# AccelRecorder.net
KiCad netlist of a schematic drawn in EAGLE
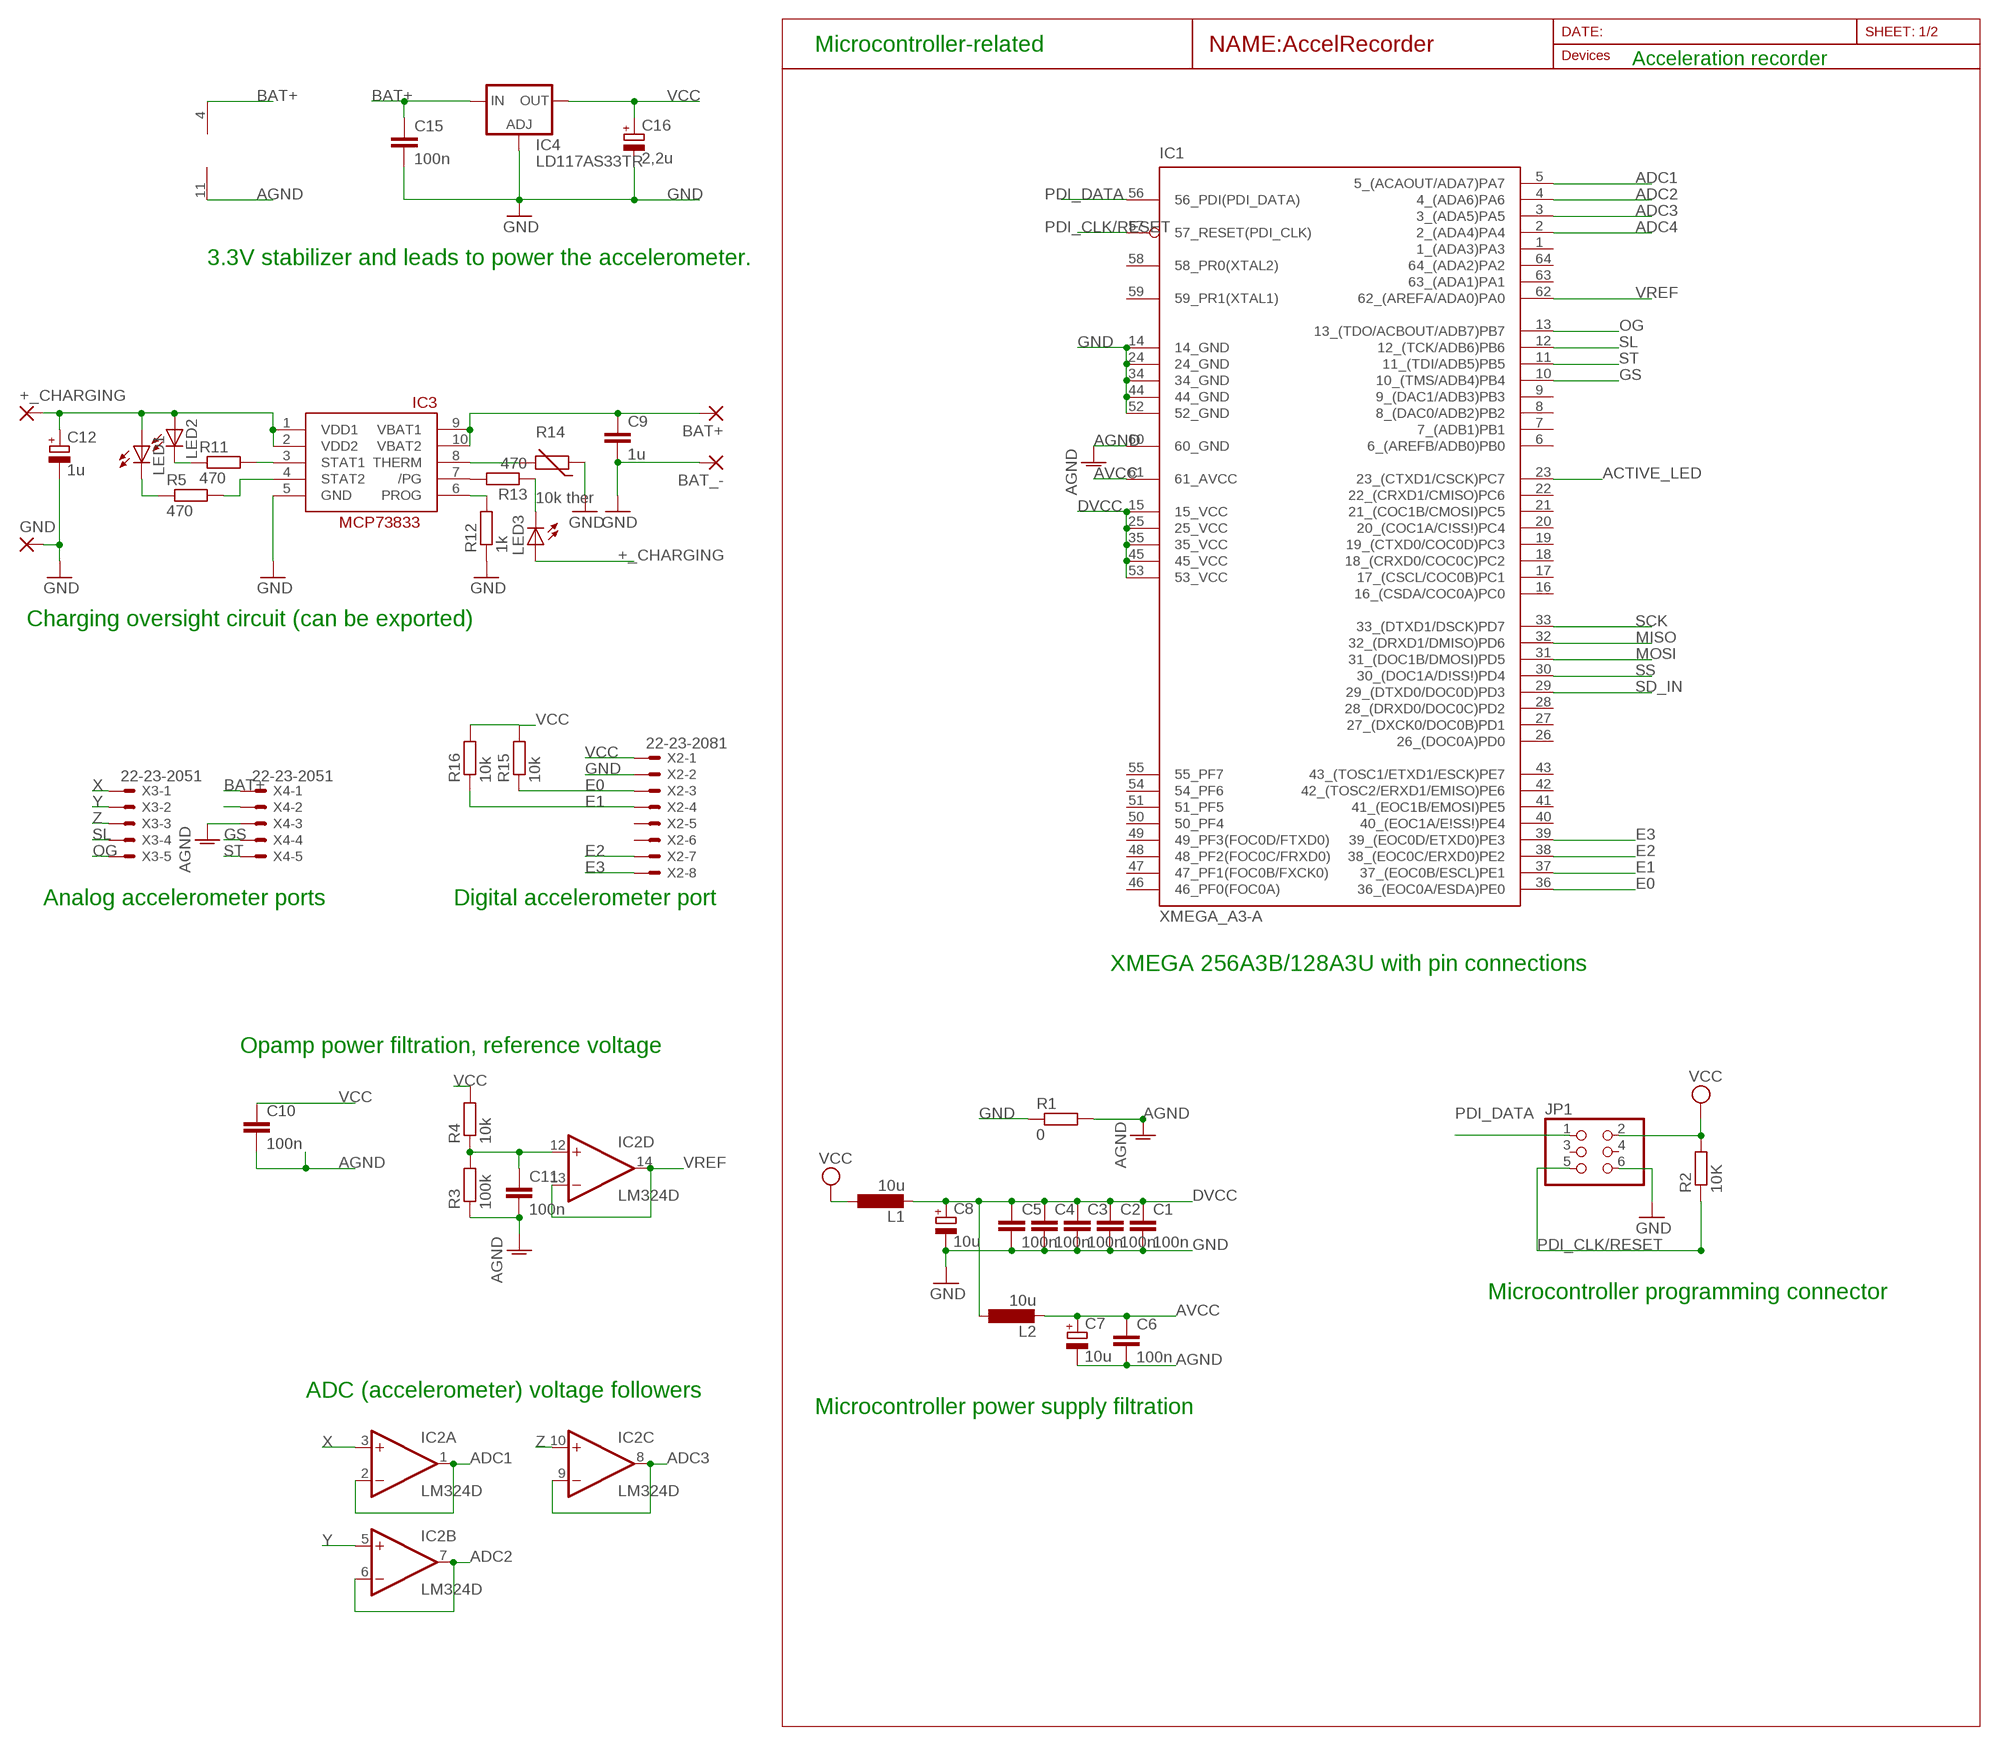
[diagram p0: schematic, sheet 1]
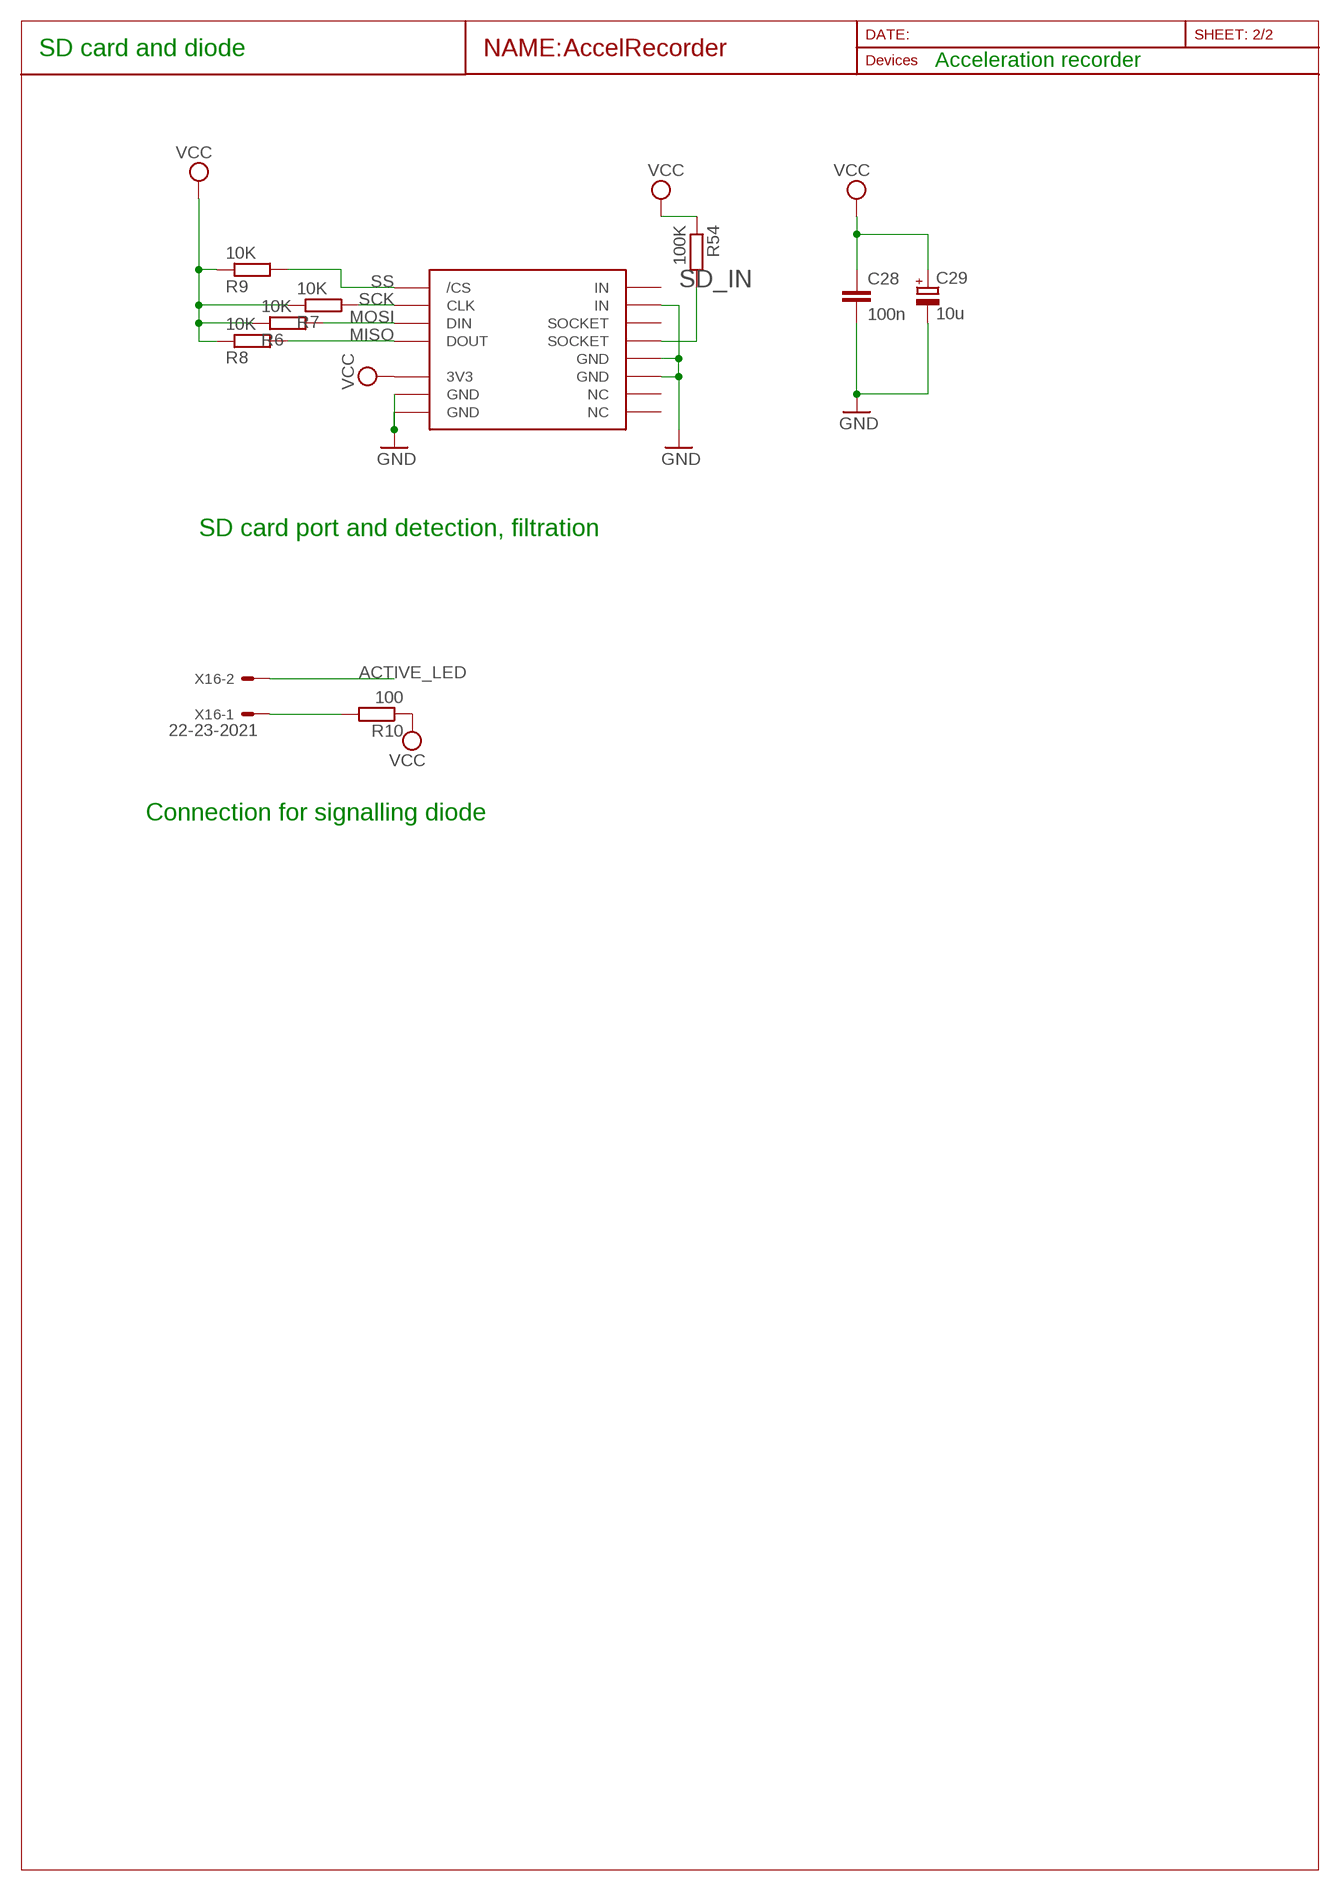
[diagram p1: schematic, sheet 2]

(export (version "E")
  (design (tool "Eeschema 10.0.6"))
  (components
    (comp (ref "+_CHARGING")
      (value "SMD2")
      (footprint "eagle-import:SMD1,27-2,54")
      (libsource (lib "eagle-import") (part "SMD2"))
    )
    (comp (ref "BAT+")
      (value "SMD2")
      (footprint "eagle-import:SMD1,27-2,54")
      (libsource (lib "eagle-import") (part "SMD2"))
    )
    (comp (ref "BAT_-")
      (value "SMD2")
      (footprint "eagle-import:SMD1,27-2,54")
      (libsource (lib "eagle-import") (part "SMD2"))
    )
    (comp (ref "C1")
      (value "100n")
      (footprint "eagle-import:C0805K")
      (libsource (lib "eagle-import") (part "C-EUC0805K"))
    )
    (comp (ref "C2")
      (value "100n")
      (footprint "eagle-import:C0805K")
      (libsource (lib "eagle-import") (part "C-EUC0805K"))
    )
    (comp (ref "C3")
      (value "100n")
      (footprint "eagle-import:C0805K")
      (libsource (lib "eagle-import") (part "C-EUC0805K"))
    )
    (comp (ref "C4")
      (value "100n")
      (footprint "eagle-import:C0805K")
      (libsource (lib "eagle-import") (part "C-EUC0805K"))
    )
    (comp (ref "C5")
      (value "100n")
      (footprint "eagle-import:C0805K")
      (libsource (lib "eagle-import") (part "C-EUC0805K"))
    )
    (comp (ref "C6")
      (value "100n")
      (footprint "eagle-import:C0805K")
      (libsource (lib "eagle-import") (part "C-EUC0805K"))
    )
    (comp (ref "C7")
      (value "10u")
      (footprint "eagle-import:SANYO-OSCON_SMD_B6")
      (libsource (lib "eagle-import") (part "CPOL-EUSANYO_SMD_B6"))
    )
    (comp (ref "C8")
      (value "10u")
      (footprint "eagle-import:SANYO-OSCON_SMD_B6")
      (libsource (lib "eagle-import") (part "CPOL-EUSANYO_SMD_B6"))
    )
    (comp (ref "C9")
      (value "1u")
      (footprint "eagle-import:C1206")
      (libsource (lib "eagle-import") (part "C-EUC1206"))
    )
    (comp (ref "C10")
      (value "100n")
      (footprint "eagle-import:C0805")
      (libsource (lib "eagle-import") (part "C-EUC0805"))
    )
    (comp (ref "C11")
      (value "100n")
      (footprint "eagle-import:C0805")
      (libsource (lib "eagle-import") (part "C-EUC0805"))
    )
    (comp (ref "C12")
      (value "1u")
      (footprint "eagle-import:SANYO-OSCON_SMD_B6")
      (libsource (lib "eagle-import") (part "CPOL-EUSANYO_SMD_B6"))
    )
    (comp (ref "C15")
      (value "100n")
      (footprint "eagle-import:C0805K")
      (libsource (lib "eagle-import") (part "C-EUC0805K"))
    )
    (comp (ref "C16")
      (value "2,2u")
      (footprint "eagle-import:SANYO-OSCON_SMD_B6")
      (libsource (lib "eagle-import") (part "CPOL-EUSANYO_SMD_B6"))
    )
    (comp (ref "GND")
      (value "SMD2")
      (footprint "eagle-import:SMD1,27-2,54")
      (libsource (lib "eagle-import") (part "SMD2"))
    )
    (comp (ref "IC1")
      (value "XMEGA_A3-A")
      (footprint "eagle-import:TQFP64")
      (libsource (lib "eagle-import") (part "XMEGA_A3-A"))
    )
    (comp (ref "IC2")
      (value "LM324D")
      (footprint "eagle-import:SO14")
      (libsource (lib "eagle-import") (part "LM324D"))
    )
    (comp (ref "IC3")
      (value "MCP73833-UN")
      (footprint "eagle-import:MSOP10")
      (libsource (lib "eagle-import") (part "MCP73833-UN"))
    )
    (comp (ref "IC4")
      (value "LD117AS33TR")
      (footprint "eagle-import:SOT223")
      (libsource (lib "eagle-import") (part "LD117A?S33TR"))
    )
    (comp (ref "JP1")
      (value "PINHD-2X3")
      (footprint "eagle-import:2X03")
      (libsource (lib "eagle-import") (part "PINHD-2X3"))
    )
    (comp (ref "L1")
      (value "10u")
      (footprint "eagle-import:L3225M")
      (libsource (lib "eagle-import") (part "L-EUL3225M"))
    )
    (comp (ref "L2")
      (value "10u")
      (footprint "eagle-import:L3225M")
      (libsource (lib "eagle-import") (part "L-EUL3225M"))
    )
    (comp (ref "LED1")
      (value "LED3MM")
      (footprint "eagle-import:LED3MM")
      (libsource (lib "eagle-import") (part "LED3MM"))
    )
    (comp (ref "LED2")
      (value "LED3MM")
      (footprint "eagle-import:LED3MM")
      (libsource (lib "eagle-import") (part "LED3MM"))
    )
    (comp (ref "LED3")
      (value "LED3MM")
      (footprint "eagle-import:LED3MM")
      (libsource (lib "eagle-import") (part "LED3MM"))
    )
    (comp (ref "R1")
      (value "0")
      (footprint "eagle-import:M1206")
      (libsource (lib "eagle-import") (part "resistor_R-EU_M1206"))
    )
    (comp (ref "R2")
      (value "10K")
      (footprint "eagle-import:M1206")
      (libsource (lib "eagle-import") (part "resistor_R-EU_M1206"))
    )
    (comp (ref "R3")
      (value "100k")
      (footprint "eagle-import:M1206")
      (libsource (lib "eagle-import") (part "resistor_R-EU_M1206"))
    )
    (comp (ref "R4")
      (value "10k")
      (footprint "eagle-import:M1206")
      (libsource (lib "eagle-import") (part "resistor_R-EU_M1206"))
    )
    (comp (ref "R5")
      (value "470")
      (footprint "eagle-import:R0805")
      (libsource (lib "eagle-import") (part "R-EU_R0805"))
    )
    (comp (ref "R11")
      (value "470")
      (footprint "eagle-import:R0805")
      (libsource (lib "eagle-import") (part "R-EU_R0805"))
    )
    (comp (ref "R12")
      (value "1k")
      (footprint "eagle-import:R0805")
      (libsource (lib "eagle-import") (part "R-EU_R0805"))
    )
    (comp (ref "R13")
      (value "470")
      (footprint "eagle-import:R0805")
      (libsource (lib "eagle-import") (part "R-EU_R0805"))
    )
    (comp (ref "R14")
      (value "10k ther")
      (footprint "eagle-import:RS-2,5")
      (libsource (lib "eagle-import") (part "THERMISTOR-2,5"))
    )
    (comp (ref "R15")
      (value "10k")
      (footprint "eagle-import:M1206")
      (libsource (lib "eagle-import") (part "resistor_R-EU_M1206"))
    )
    (comp (ref "R16")
      (value "10k")
      (footprint "eagle-import:M1206")
      (libsource (lib "eagle-import") (part "resistor_R-EU_M1206"))
    )
    (comp (ref "X2")
      (value "22-23-2081")
      (footprint "eagle-import:22-23-2081")
      (fields (field (name "MF") "MOLEX"))
      (libsource (lib "eagle-import") (part "22-23-2081"))
    )
    (comp (ref "X3")
      (value "22-23-2051")
      (footprint "eagle-import:22-23-2051")
      (fields (field (name "MF") "MOLEX"))
      (libsource (lib "eagle-import") (part "22-23-2051"))
    )
    (comp (ref "X4")
      (value "22-23-2051")
      (footprint "eagle-import:22-23-2051")
      (fields (field (name "MF") "MOLEX"))
      (libsource (lib "eagle-import") (part "22-23-2051"))
    )
    (comp (ref "C28")
      (value "100n")
      (footprint "eagle-import:C0805K")
      (libsource (lib "eagle-import") (part "C-EUC0805K"))
    )
    (comp (ref "C29")
      (value "10u")
      (footprint "eagle-import:SANYO-OSCON_SMD_B6")
      (libsource (lib "eagle-import") (part "CPOL-EUSANYO_SMD_B6"))
    )
    (comp (ref "R6")
      (value "10K")
      (footprint "eagle-import:M1206")
      (libsource (lib "eagle-import") (part "resistor_R-EU_M1206"))
    )
    (comp (ref "R7")
      (value "10K")
      (footprint "eagle-import:M1206")
      (libsource (lib "eagle-import") (part "resistor_R-EU_M1206"))
    )
    (comp (ref "R8")
      (value "10K")
      (footprint "eagle-import:M1206")
      (libsource (lib "eagle-import") (part "resistor_R-EU_M1206"))
    )
    (comp (ref "R9")
      (value "10K")
      (footprint "eagle-import:M1206")
      (libsource (lib "eagle-import") (part "resistor_R-EU_M1206"))
    )
    (comp (ref "R10")
      (value "100")
      (footprint "eagle-import:M1206")
      (libsource (lib "eagle-import") (part "resistor_R-EU_M1206"))
    )
    (comp (ref "R54")
      (value "100K")
      (footprint "eagle-import:M1206")
      (libsource (lib "eagle-import") (part "resistor_R-EU_M1206"))
    )
    (comp (ref "U$1")
      (value "MMC")
      (footprint "eagle-import:MMC_SOCKET")
      (libsource (lib "eagle-import") (part "MMC"))
    )
    (comp (ref "X16")
      (value "22-23-2021")
      (footprint "eagle-import:22-23-2021")
      (fields
        (field (name "MF") "MOLEX")
        (field (name "MF_1") "MOLEX")
        (field (name "MPN") "22-23-2021")
        (field (name "OC_FARNELL") "1462926")
        (field (name "OC_NEWARK") "25C3832")
      )
      (libsource (lib "eagle-import") (part "22-23-2021"))
    )
  )
  (nets
    (net (code "1") (name "+_CHARGING") (class "Default")
      (node (ref "+_CHARGING") (pin "1") (pinfunction "P_1") (pintype "passive"))
      (node (ref "C12") (pin "+") (pinfunction "+_+") (pintype "passive"))
      (node (ref "IC3") (pin "1") (pinfunction "VDD1_1") (pintype "power_in"))
      (node (ref "IC3") (pin "2") (pinfunction "VDD2_2") (pintype "power_in"))
      (node (ref "LED1") (pin "A") (pinfunction "A_A") (pintype "passive"))
      (node (ref "LED2") (pin "A") (pinfunction "A_A") (pintype "passive"))
      (node (ref "LED3") (pin "A") (pinfunction "A_A") (pintype "passive"))
    )
    (net (code "2") (name "ACTIVE_LED") (class "Default")
      (node (ref "IC1") (pin "23") (pinfunction "23_(CTXD1/CSCK)PC7_23") (pintype "bidirectional"))
      (node (ref "X16") (pin "2") (pinfunction "S_2") (pintype "passive"))
    )
    (net (code "3") (name "ADC1") (class "Default")
      (node (ref "IC1") (pin "5") (pinfunction "5_(ACAOUT/ADA7)PA7_5") (pintype "bidirectional"))
      (node (ref "IC2") (pin "1") (pinfunction "OUT_1") (pintype "output"))
      (node (ref "IC2") (pin "2") (pinfunction "-IN_2") (pintype "input"))
    )
    (net (code "4") (name "ADC2") (class "Default")
      (node (ref "IC1") (pin "4") (pinfunction "4_(ADA6)PA6_4") (pintype "bidirectional"))
      (node (ref "IC2") (pin "6") (pinfunction "-IN_6") (pintype "input"))
      (node (ref "IC2") (pin "7") (pinfunction "OUT_7") (pintype "output"))
    )
    (net (code "5") (name "ADC3") (class "Default")
      (node (ref "IC1") (pin "3") (pinfunction "3_(ADA5)PA5_3") (pintype "bidirectional"))
      (node (ref "IC2") (pin "8") (pinfunction "OUT_8") (pintype "output"))
      (node (ref "IC2") (pin "9") (pinfunction "-IN_9") (pintype "input"))
    )
    (net (code "6") (name "ADC4") (class "Default")
      (node (ref "IC1") (pin "2") (pinfunction "2_(ADA4)PA4_2") (pintype "bidirectional"))
    )
    (net (code "7") (name "AGND") (class "Default")
      (node (ref "C10") (pin "2") (pinfunction "2_2") (pintype "passive"))
      (node (ref "C11") (pin "2") (pinfunction "2_2") (pintype "passive"))
      (node (ref "C6") (pin "2") (pinfunction "2_2") (pintype "passive"))
      (node (ref "C7") (pin "-") (pinfunction "-_-") (pintype "passive"))
      (node (ref "IC1") (pin "60") (pinfunction "60_GND_60") (pintype "bidirectional"))
      (node (ref "IC2") (pin "11") (pinfunction "V-_11") (pintype "power_in"))
      (node (ref "R1") (pin "2") (pinfunction "2_2") (pintype "passive"))
      (node (ref "R3") (pin "1") (pinfunction "1_1") (pintype "passive"))
      (node (ref "X4") (pin "3") (pinfunction "S_3") (pintype "passive"))
    )
    (net (code "8") (name "AVCC") (class "Default")
      (node (ref "C6") (pin "1") (pinfunction "1_1") (pintype "passive"))
      (node (ref "C7") (pin "+") (pinfunction "+_+") (pintype "passive"))
      (node (ref "IC1") (pin "61") (pinfunction "61_AVCC_61") (pintype "bidirectional"))
      (node (ref "L2") (pin "2") (pinfunction "2_2") (pintype "passive"))
    )
    (net (code "9") (name "BAT+") (class "Default")
      (node (ref "BAT+") (pin "1") (pinfunction "P_1") (pintype "passive"))
      (node (ref "C15") (pin "1") (pinfunction "1_1") (pintype "passive"))
      (node (ref "C9") (pin "1") (pinfunction "1_1") (pintype "passive"))
      (node (ref "IC2") (pin "4") (pinfunction "V+_4") (pintype "power_in"))
      (node (ref "IC3") (pin "10") (pinfunction "VBAT2_10") (pintype "output"))
      (node (ref "IC3") (pin "9") (pinfunction "VBAT1_9") (pintype "output"))
      (node (ref "IC4") (pin "3") (pinfunction "IN_3") (pintype "input"))
      (node (ref "X4") (pin "1") (pinfunction "S_1") (pintype "passive"))
    )
    (net (code "10") (name "DVCC") (class "Default")
      (node (ref "C1") (pin "1") (pinfunction "1_1") (pintype "passive"))
      (node (ref "C2") (pin "1") (pinfunction "1_1") (pintype "passive"))
      (node (ref "C3") (pin "1") (pinfunction "1_1") (pintype "passive"))
      (node (ref "C4") (pin "1") (pinfunction "1_1") (pintype "passive"))
      (node (ref "C5") (pin "1") (pinfunction "1_1") (pintype "passive"))
      (node (ref "C8") (pin "+") (pinfunction "+_+") (pintype "passive"))
      (node (ref "IC1") (pin "15") (pinfunction "15_VCC_15") (pintype "bidirectional"))
      (node (ref "IC1") (pin "25") (pinfunction "25_VCC_25") (pintype "bidirectional"))
      (node (ref "IC1") (pin "35") (pinfunction "35_VCC_35") (pintype "bidirectional"))
      (node (ref "IC1") (pin "45") (pinfunction "45_VCC_45") (pintype "bidirectional"))
      (node (ref "IC1") (pin "53") (pinfunction "53_VCC_53") (pintype "bidirectional"))
      (node (ref "L1") (pin "2") (pinfunction "2_2") (pintype "passive"))
      (node (ref "L2") (pin "1") (pinfunction "1_1") (pintype "passive"))
    )
    (net (code "11") (name "E0") (class "Default")
      (node (ref "IC1") (pin "36") (pinfunction "36_(EOC0A/ESDA)PE0_36") (pintype "bidirectional"))
      (node (ref "R15") (pin "1") (pinfunction "1_1") (pintype "passive"))
      (node (ref "X2") (pin "3") (pinfunction "S_3") (pintype "passive"))
    )
    (net (code "12") (name "E1") (class "Default")
      (node (ref "IC1") (pin "37") (pinfunction "37_(EOC0B/ESCL)PE1_37") (pintype "bidirectional"))
      (node (ref "R16") (pin "1") (pinfunction "1_1") (pintype "passive"))
      (node (ref "X2") (pin "4") (pinfunction "S_4") (pintype "passive"))
    )
    (net (code "13") (name "E2") (class "Default")
      (node (ref "IC1") (pin "38") (pinfunction "38_(EOC0C/ERXD0)PE2_38") (pintype "bidirectional"))
      (node (ref "X2") (pin "7") (pinfunction "S_7") (pintype "passive"))
    )
    (net (code "14") (name "E3") (class "Default")
      (node (ref "IC1") (pin "39") (pinfunction "39_(EOC0D/ETXD0)PE3_39") (pintype "bidirectional"))
      (node (ref "X2") (pin "8") (pinfunction "S_8") (pintype "passive"))
    )
    (net (code "15") (name "GND") (class "Default")
      (node (ref "BAT_-") (pin "1") (pinfunction "P_1") (pintype "passive"))
      (node (ref "C1") (pin "2") (pinfunction "2_2") (pintype "passive"))
      (node (ref "C12") (pin "-") (pinfunction "-_-") (pintype "passive"))
      (node (ref "C15") (pin "2") (pinfunction "2_2") (pintype "passive"))
      (node (ref "C16") (pin "-") (pinfunction "-_-") (pintype "passive"))
      (node (ref "C2") (pin "2") (pinfunction "2_2") (pintype "passive"))
      (node (ref "C28") (pin "2") (pinfunction "2_2") (pintype "passive"))
      (node (ref "C29") (pin "-") (pinfunction "-_-") (pintype "passive"))
      (node (ref "C3") (pin "2") (pinfunction "2_2") (pintype "passive"))
      (node (ref "C4") (pin "2") (pinfunction "2_2") (pintype "passive"))
      (node (ref "C5") (pin "2") (pinfunction "2_2") (pintype "passive"))
      (node (ref "C8") (pin "-") (pinfunction "-_-") (pintype "passive"))
      (node (ref "C9") (pin "2") (pinfunction "2_2") (pintype "passive"))
      (node (ref "GND") (pin "1") (pinfunction "P_1") (pintype "passive"))
      (node (ref "IC1") (pin "14") (pinfunction "14_GND_14") (pintype "bidirectional"))
      (node (ref "IC1") (pin "24") (pinfunction "24_GND_24") (pintype "bidirectional"))
      (node (ref "IC1") (pin "34") (pinfunction "34_GND_34") (pintype "bidirectional"))
      (node (ref "IC1") (pin "44") (pinfunction "44_GND_44") (pintype "bidirectional"))
      (node (ref "IC1") (pin "52") (pinfunction "52_GND_52") (pintype "bidirectional"))
      (node (ref "IC3") (pin "5") (pinfunction "GND_5") (pintype "power_in"))
      (node (ref "IC4") (pin "1") (pinfunction "ADJ_1") (pintype "input"))
      (node (ref "JP1") (pin "6") (pinfunction "6_6") (pintype "passive"))
      (node (ref "R1") (pin "1") (pinfunction "1_1") (pintype "passive"))
      (node (ref "R12") (pin "1") (pinfunction "1_1") (pintype "passive"))
      (node (ref "R14") (pin "1") (pinfunction "1_1") (pintype "passive"))
      (node (ref "U$1") (pin "GND@1") (pinfunction "GND_GND@1") (pintype "power_in"))
      (node (ref "U$1") (pin "GND@2") (pinfunction "GND_GND@2") (pintype "power_in"))
      (node (ref "U$1") (pin "GND@3") (pinfunction "GND_GND@3") (pintype "power_in"))
      (node (ref "U$1") (pin "GND@4") (pinfunction "GND_GND@4") (pintype "power_in"))
      (node (ref "U$1") (pin "IN@2") (pinfunction "IN_IN@2") (pintype "input"))
      (node (ref "X2") (pin "2") (pinfunction "S_2") (pintype "passive"))
    )
    (net (code "16") (name "GS") (class "Default")
      (node (ref "IC1") (pin "10") (pinfunction "10_(TMS/ADB4)PB4_10") (pintype "bidirectional"))
      (node (ref "X4") (pin "4") (pinfunction "S_4") (pintype "passive"))
    )
    (net (code "17") (name "MISO") (class "Default")
      (node (ref "IC1") (pin "32") (pinfunction "32_(DRXD1/DMISO)PD6_32") (pintype "bidirectional"))
      (node (ref "R8") (pin "2") (pinfunction "2_2") (pintype "passive"))
      (node (ref "U$1") (pin "DOUT") (pinfunction "DOUT_DOUT") (pintype "output"))
    )
    (net (code "18") (name "MOSI") (class "Default")
      (node (ref "IC1") (pin "31") (pinfunction "31_(DOC1B/DMOSI)PD5_31") (pintype "bidirectional"))
      (node (ref "R6") (pin "2") (pinfunction "2_2") (pintype "passive"))
      (node (ref "U$1") (pin "DIN") (pinfunction "DIN_DIN") (pintype "input"))
    )
    (net (code "19") (name "Net-(IC2D-+IN)") (class "Default")
      (node (ref "C11") (pin "1") (pinfunction "1_1") (pintype "passive"))
      (node (ref "IC2") (pin "12") (pinfunction "+IN_12") (pintype "input"))
      (node (ref "R3") (pin "2") (pinfunction "2_2") (pintype "passive"))
      (node (ref "R4") (pin "1") (pinfunction "1_1") (pintype "passive"))
    )
    (net (code "20") (name "Net-(IC3-PROG)") (class "Default")
      (node (ref "IC3") (pin "6") (pinfunction "PROG_6") (pintype "input"))
      (node (ref "R12") (pin "2") (pinfunction "2_2") (pintype "passive"))
    )
    (net (code "21") (name "Net-(IC3-STAT1)") (class "Default")
      (node (ref "IC3") (pin "3") (pinfunction "STAT1_3") (pintype "passive"))
      (node (ref "R11") (pin "2") (pinfunction "2_2") (pintype "passive"))
    )
    (net (code "22") (name "Net-(IC3-STAT2)") (class "Default")
      (node (ref "IC3") (pin "4") (pinfunction "STAT2_4") (pintype "passive"))
      (node (ref "R5") (pin "2") (pinfunction "2_2") (pintype "passive"))
    )
    (net (code "23") (name "Net-(IC3-THERM)") (class "Default")
      (node (ref "IC3") (pin "8") (pinfunction "THERM_8") (pintype "bidirectional"))
      (node (ref "R14") (pin "2") (pinfunction "2_2") (pintype "passive"))
    )
    (net (code "24") (name "Net-(IC3-{slash}PG)") (class "Default")
      (node (ref "IC3") (pin "7") (pinfunction "/PG_7") (pintype "passive"))
      (node (ref "R13") (pin "2") (pinfunction "2_2") (pintype "passive"))
    )
    (net (code "25") (name "Net-(LED1-C)") (class "Default")
      (node (ref "LED1") (pin "K") (pinfunction "C_K") (pintype "passive"))
      (node (ref "R5") (pin "1") (pinfunction "1_1") (pintype "passive"))
    )
    (net (code "26") (name "Net-(LED2-C)") (class "Default")
      (node (ref "LED2") (pin "K") (pinfunction "C_K") (pintype "passive"))
      (node (ref "R11") (pin "1") (pinfunction "1_1") (pintype "passive"))
    )
    (net (code "27") (name "Net-(LED3-C)") (class "Default")
      (node (ref "LED3") (pin "K") (pinfunction "C_K") (pintype "passive"))
      (node (ref "R13") (pin "1") (pinfunction "1_1") (pintype "passive"))
    )
    (net (code "28") (name "Net-(X16A-S)") (class "Default")
      (node (ref "R10") (pin "2") (pinfunction "2_2") (pintype "passive"))
      (node (ref "X16") (pin "1") (pinfunction "S_1") (pintype "passive"))
    )
    (net (code "29") (name "OG") (class "Default")
      (node (ref "IC1") (pin "13") (pinfunction "13_(TDO/ACBOUT/ADB7)PB7_13") (pintype "bidirectional"))
      (node (ref "X3") (pin "5") (pinfunction "S_5") (pintype "passive"))
    )
    (net (code "30") (name "PDI_CLK{slash}RESET") (class "Default")
      (node (ref "IC1") (pin "57") (pinfunction "57_RESET(PDI_CLK)_57") (pintype "bidirectional"))
      (node (ref "JP1") (pin "5") (pinfunction "5_5") (pintype "passive"))
      (node (ref "R2") (pin "1") (pinfunction "1_1") (pintype "passive"))
    )
    (net (code "31") (name "PDI_DATA") (class "Default")
      (node (ref "IC1") (pin "56") (pinfunction "56_PDI(PDI_DATA)_56") (pintype "bidirectional"))
      (node (ref "JP1") (pin "1") (pinfunction "1_1") (pintype "passive"))
    )
    (net (code "32") (name "SCK") (class "Default")
      (node (ref "IC1") (pin "33") (pinfunction "33_(DTXD1/DSCK)PD7_33") (pintype "bidirectional"))
      (node (ref "R7") (pin "2") (pinfunction "2_2") (pintype "passive"))
      (node (ref "U$1") (pin "CLK") (pinfunction "CLK_CLK") (pintype "input"))
    )
    (net (code "33") (name "SD_IN") (class "Default")
      (node (ref "IC1") (pin "29") (pinfunction "29_(DTXD0/DOC0D)PD3_29") (pintype "bidirectional"))
      (node (ref "R54") (pin "2") (pinfunction "2_2") (pintype "passive"))
      (node (ref "U$1") (pin "P$2") (pinfunction "SOCKET_P$2") (pintype "input"))
    )
    (net (code "34") (name "SL") (class "Default")
      (node (ref "IC1") (pin "12") (pinfunction "12_(TCK/ADB6)PB6_12") (pintype "bidirectional"))
      (node (ref "X3") (pin "4") (pinfunction "S_4") (pintype "passive"))
    )
    (net (code "35") (name "SS") (class "Default")
      (node (ref "IC1") (pin "30") (pinfunction "30_(DOC1A/D\\~{SS\\})PD4_30") (pintype "bidirectional"))
      (node (ref "R9") (pin "2") (pinfunction "2_2") (pintype "passive"))
      (node (ref "U$1") (pin "/CS") (pinfunction "/CS_/CS") (pintype "input"))
    )
    (net (code "36") (name "ST") (class "Default")
      (node (ref "IC1") (pin "11") (pinfunction "11_(TDI/ADB5)PB5_11") (pintype "bidirectional"))
      (node (ref "X4") (pin "5") (pinfunction "S_5") (pintype "passive"))
    )
    (net (code "37") (name "VCC") (class "Default")
      (node (ref "C10") (pin "1") (pinfunction "1_1") (pintype "passive"))
      (node (ref "C16") (pin "+") (pinfunction "+_+") (pintype "passive"))
      (node (ref "C28") (pin "1") (pinfunction "1_1") (pintype "passive"))
      (node (ref "C29") (pin "+") (pinfunction "+_+") (pintype "passive"))
      (node (ref "IC4") (pin "4") (pinfunction "OUT_4") (pintype "passive"))
      (node (ref "JP1") (pin "2") (pinfunction "2_2") (pintype "passive"))
      (node (ref "L1") (pin "1") (pinfunction "1_1") (pintype "passive"))
      (node (ref "R10") (pin "1") (pinfunction "1_1") (pintype "passive"))
      (node (ref "R15") (pin "2") (pinfunction "2_2") (pintype "passive"))
      (node (ref "R16") (pin "2") (pinfunction "2_2") (pintype "passive"))
      (node (ref "R2") (pin "2") (pinfunction "2_2") (pintype "passive"))
      (node (ref "R4") (pin "2") (pinfunction "2_2") (pintype "passive"))
      (node (ref "R54") (pin "1") (pinfunction "1_1") (pintype "passive"))
      (node (ref "R6") (pin "1") (pinfunction "1_1") (pintype "passive"))
      (node (ref "R7") (pin "1") (pinfunction "1_1") (pintype "passive"))
      (node (ref "R8") (pin "1") (pinfunction "1_1") (pintype "passive"))
      (node (ref "R9") (pin "1") (pinfunction "1_1") (pintype "passive"))
      (node (ref "U$1") (pin "3V3") (pinfunction "3V3_3V3") (pintype "power_in"))
      (node (ref "X2") (pin "1") (pinfunction "S_1") (pintype "passive"))
    )
    (net (code "38") (name "VREF") (class "Default")
      (node (ref "IC1") (pin "62") (pinfunction "62_(AREFA/ADA0)PA0_62") (pintype "bidirectional"))
      (node (ref "IC2") (pin "13") (pinfunction "-IN_13") (pintype "input"))
      (node (ref "IC2") (pin "14") (pinfunction "OUT_14") (pintype "output"))
    )
    (net (code "39") (name "X") (class "Default")
      (node (ref "IC2") (pin "3") (pinfunction "+IN_3") (pintype "input"))
      (node (ref "X3") (pin "1") (pinfunction "S_1") (pintype "passive"))
    )
    (net (code "40") (name "Y") (class "Default")
      (node (ref "IC2") (pin "5") (pinfunction "+IN_5") (pintype "input"))
      (node (ref "X3") (pin "2") (pinfunction "S_2") (pintype "passive"))
    )
    (net (code "41") (name "Z") (class "Default")
      (node (ref "IC2") (pin "10") (pinfunction "+IN_10") (pintype "input"))
      (node (ref "X3") (pin "3") (pinfunction "S_3") (pintype "passive"))
    )
    (net (code "42") (name "unconnected-(IC1-1_(ADA3)PA3-Pad1)") (class "Default")
      (node (ref "IC1") (pin "1") (pinfunction "1_(ADA3)PA3_1") (pintype "bidirectional"))
    )
    (net (code "43") (name "unconnected-(IC1-6_(AREFB{slash}ADB0)PB0-Pad6)") (class "Default")
      (node (ref "IC1") (pin "6") (pinfunction "6_(AREFB/ADB0)PB0_6") (pintype "bidirectional"))
    )
    (net (code "44") (name "unconnected-(IC1-7_(ADB1)PB1-Pad7)") (class "Default")
      (node (ref "IC1") (pin "7") (pinfunction "7_(ADB1)PB1_7") (pintype "bidirectional"))
    )
    (net (code "45") (name "unconnected-(IC1-8_(DAC0{slash}ADB2)PB2-Pad8)") (class "Default")
      (node (ref "IC1") (pin "8") (pinfunction "8_(DAC0/ADB2)PB2_8") (pintype "bidirectional"))
    )
    (net (code "46") (name "unconnected-(IC1-9_(DAC1{slash}ADB3)PB3-Pad9)") (class "Default")
      (node (ref "IC1") (pin "9") (pinfunction "9_(DAC1/ADB3)PB3_9") (pintype "bidirectional"))
    )
    (net (code "47") (name "unconnected-(IC1-16_(CSDA{slash}COC0A)PC0-Pad16)") (class "Default")
      (node (ref "IC1") (pin "16") (pinfunction "16_(CSDA/COC0A)PC0_16") (pintype "bidirectional"))
    )
    (net (code "48") (name "unconnected-(IC1-17_(CSCL{slash}COC0B)PC1-Pad17)") (class "Default")
      (node (ref "IC1") (pin "17") (pinfunction "17_(CSCL/COC0B)PC1_17") (pintype "bidirectional"))
    )
    (net (code "49") (name "unconnected-(IC1-18_(CRXD0{slash}COC0C)PC2-Pad18)") (class "Default")
      (node (ref "IC1") (pin "18") (pinfunction "18_(CRXD0/COC0C)PC2_18") (pintype "bidirectional"))
    )
    (net (code "50") (name "unconnected-(IC1-19_(CTXD0{slash}COC0D)PC3-Pad19)") (class "Default")
      (node (ref "IC1") (pin "19") (pinfunction "19_(CTXD0/COC0D)PC3_19") (pintype "bidirectional"))
    )
    (net (code "51") (name "unconnected-(IC1-20_(COC1A{slash}C\\~{SS\\})PC4-Pad20)") (class "Default")
      (node (ref "IC1") (pin "20") (pinfunction "20_(COC1A/C\\~{SS\\})PC4_20") (pintype "bidirectional"))
    )
    (net (code "52") (name "unconnected-(IC1-21_(COC1B{slash}CMOSI)PC5-Pad21)") (class "Default")
      (node (ref "IC1") (pin "21") (pinfunction "21_(COC1B/CMOSI)PC5_21") (pintype "bidirectional"))
    )
    (net (code "53") (name "unconnected-(IC1-22_(CRXD1{slash}CMISO)PC6-Pad22)") (class "Default")
      (node (ref "IC1") (pin "22") (pinfunction "22_(CRXD1/CMISO)PC6_22") (pintype "bidirectional"))
    )
    (net (code "54") (name "unconnected-(IC1-26_(DOC0A)PD0-Pad26)") (class "Default")
      (node (ref "IC1") (pin "26") (pinfunction "26_(DOC0A)PD0_26") (pintype "bidirectional"))
    )
    (net (code "55") (name "unconnected-(IC1-27_(DXCK0{slash}DOC0B)PD1-Pad27)") (class "Default")
      (node (ref "IC1") (pin "27") (pinfunction "27_(DXCK0/DOC0B)PD1_27") (pintype "bidirectional"))
    )
    (net (code "56") (name "unconnected-(IC1-28_(DRXD0{slash}DOC0C)PD2-Pad28)") (class "Default")
      (node (ref "IC1") (pin "28") (pinfunction "28_(DRXD0/DOC0C)PD2_28") (pintype "bidirectional"))
    )
    (net (code "57") (name "unconnected-(IC1-40_(EOC1A{slash}E\\~{SS\\})PE4-Pad40)") (class "Default")
      (node (ref "IC1") (pin "40") (pinfunction "40_(EOC1A/E\\~{SS\\})PE4_40") (pintype "bidirectional"))
    )
    (net (code "58") (name "unconnected-(IC1-41_(EOC1B{slash}EMOSI)PE5-Pad41)") (class "Default")
      (node (ref "IC1") (pin "41") (pinfunction "41_(EOC1B/EMOSI)PE5_41") (pintype "bidirectional"))
    )
    (net (code "59") (name "unconnected-(IC1-42_(TOSC2{slash}ERXD1{slash}EMISO)PE6-Pad42)") (class "Default")
      (node (ref "IC1") (pin "42") (pinfunction "42_(TOSC2/ERXD1/EMISO)PE6_42") (pintype "bidirectional"))
    )
    (net (code "60") (name "unconnected-(IC1-43_(TOSC1{slash}ETXD1{slash}ESCK)PE7-Pad43)") (class "Default")
      (node (ref "IC1") (pin "43") (pinfunction "43_(TOSC1/ETXD1/ESCK)PE7_43") (pintype "bidirectional"))
    )
    (net (code "61") (name "unconnected-(IC1-46_PF0(FOC0A)-Pad46)") (class "Default")
      (node (ref "IC1") (pin "46") (pinfunction "46_PF0(FOC0A)_46") (pintype "bidirectional"))
    )
    (net (code "62") (name "unconnected-(IC1-47_PF1(FOC0B{slash}FXCK0)-Pad47)") (class "Default")
      (node (ref "IC1") (pin "47") (pinfunction "47_PF1(FOC0B/FXCK0)_47") (pintype "bidirectional"))
    )
    (net (code "63") (name "unconnected-(IC1-48_PF2(FOC0C{slash}FRXD0)-Pad48)") (class "Default")
      (node (ref "IC1") (pin "48") (pinfunction "48_PF2(FOC0C/FRXD0)_48") (pintype "bidirectional"))
    )
    (net (code "64") (name "unconnected-(IC1-49_PF3(FOC0D{slash}FTXD0)-Pad49)") (class "Default")
      (node (ref "IC1") (pin "49") (pinfunction "49_PF3(FOC0D/FTXD0)_49") (pintype "bidirectional"))
    )
    (net (code "65") (name "unconnected-(IC1-50_PF4-Pad50)") (class "Default")
      (node (ref "IC1") (pin "50") (pinfunction "50_PF4_50") (pintype "bidirectional"))
    )
    (net (code "66") (name "unconnected-(IC1-51_PF5-Pad51)") (class "Default")
      (node (ref "IC1") (pin "51") (pinfunction "51_PF5_51") (pintype "bidirectional"))
    )
    (net (code "67") (name "unconnected-(IC1-54_PF6-Pad54)") (class "Default")
      (node (ref "IC1") (pin "54") (pinfunction "54_PF6_54") (pintype "bidirectional"))
    )
    (net (code "68") (name "unconnected-(IC1-55_PF7-Pad55)") (class "Default")
      (node (ref "IC1") (pin "55") (pinfunction "55_PF7_55") (pintype "bidirectional"))
    )
    (net (code "69") (name "unconnected-(IC1-58_PR0(XTAL2)-Pad58)") (class "Default")
      (node (ref "IC1") (pin "58") (pinfunction "58_PR0(XTAL2)_58") (pintype "bidirectional"))
    )
    (net (code "70") (name "unconnected-(IC1-59_PR1(XTAL1)-Pad59)") (class "Default")
      (node (ref "IC1") (pin "59") (pinfunction "59_PR1(XTAL1)_59") (pintype "bidirectional"))
    )
    (net (code "71") (name "unconnected-(IC1-63_(ADA1)PA1-Pad63)") (class "Default")
      (node (ref "IC1") (pin "63") (pinfunction "63_(ADA1)PA1_63") (pintype "bidirectional"))
    )
    (net (code "72") (name "unconnected-(IC1-64_(ADA2)PA2-Pad64)") (class "Default")
      (node (ref "IC1") (pin "64") (pinfunction "64_(ADA2)PA2_64") (pintype "bidirectional"))
    )
    (net (code "73") (name "unconnected-(JP1-Pad3)") (class "Default")
      (node (ref "JP1") (pin "3") (pinfunction "3_3") (pintype "passive"))
    )
    (net (code "74") (name "unconnected-(JP1-Pad4)") (class "Default")
      (node (ref "JP1") (pin "4") (pinfunction "4_4") (pintype "passive"))
    )
    (net (code "75") (name "unconnected-(U$1-IN-PadIN@1)") (class "Default")
      (node (ref "U$1") (pin "IN@1") (pinfunction "IN_IN@1") (pintype "input"))
    )
    (net (code "76") (name "unconnected-(U$1-NC-PadNC@1)") (class "Default")
      (node (ref "U$1") (pin "NC@1") (pinfunction "NC_NC@1") (pintype "no_connect"))
    )
    (net (code "77") (name "unconnected-(U$1-NC-PadNC@2)") (class "Default")
      (node (ref "U$1") (pin "NC@2") (pinfunction "NC_NC@2") (pintype "no_connect"))
    )
    (net (code "78") (name "unconnected-(U$1-SOCKET-PadP$1)") (class "Default")
      (node (ref "U$1") (pin "P$1") (pinfunction "SOCKET_P$1") (pintype "input"))
    )
    (net (code "79") (name "unconnected-(X2E-S-Pad5)") (class "Default")
      (node (ref "X2") (pin "5") (pinfunction "S_5") (pintype "passive"))
    )
    (net (code "80") (name "unconnected-(X2F-S-Pad6)") (class "Default")
      (node (ref "X2") (pin "6") (pinfunction "S_6") (pintype "passive"))
    )
    (net (code "81") (name "unconnected-(X4B-S-Pad2)") (class "Default")
      (node (ref "X4") (pin "2") (pinfunction "S_2") (pintype "passive"))
    )
  )
)
